# Audio-DAC-A.net
KiCad netlist of a schematic drawn in EAGLE
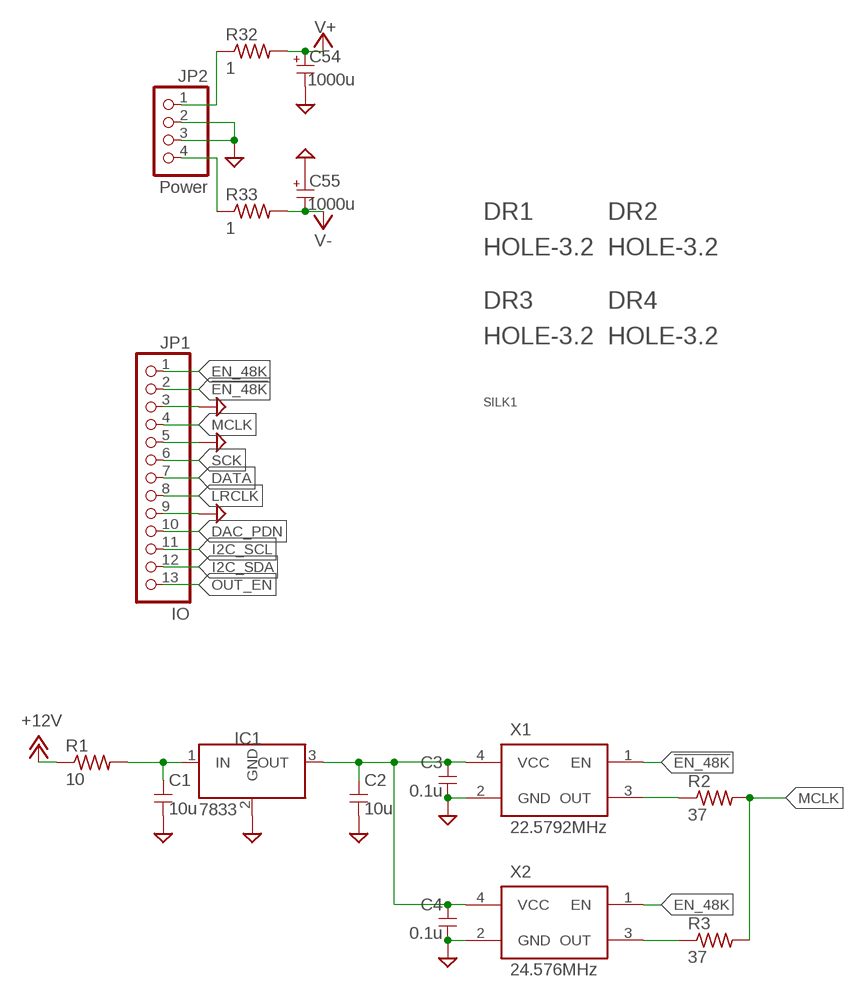
[diagram p0: schematic, sheet 1, part 1 of 2]
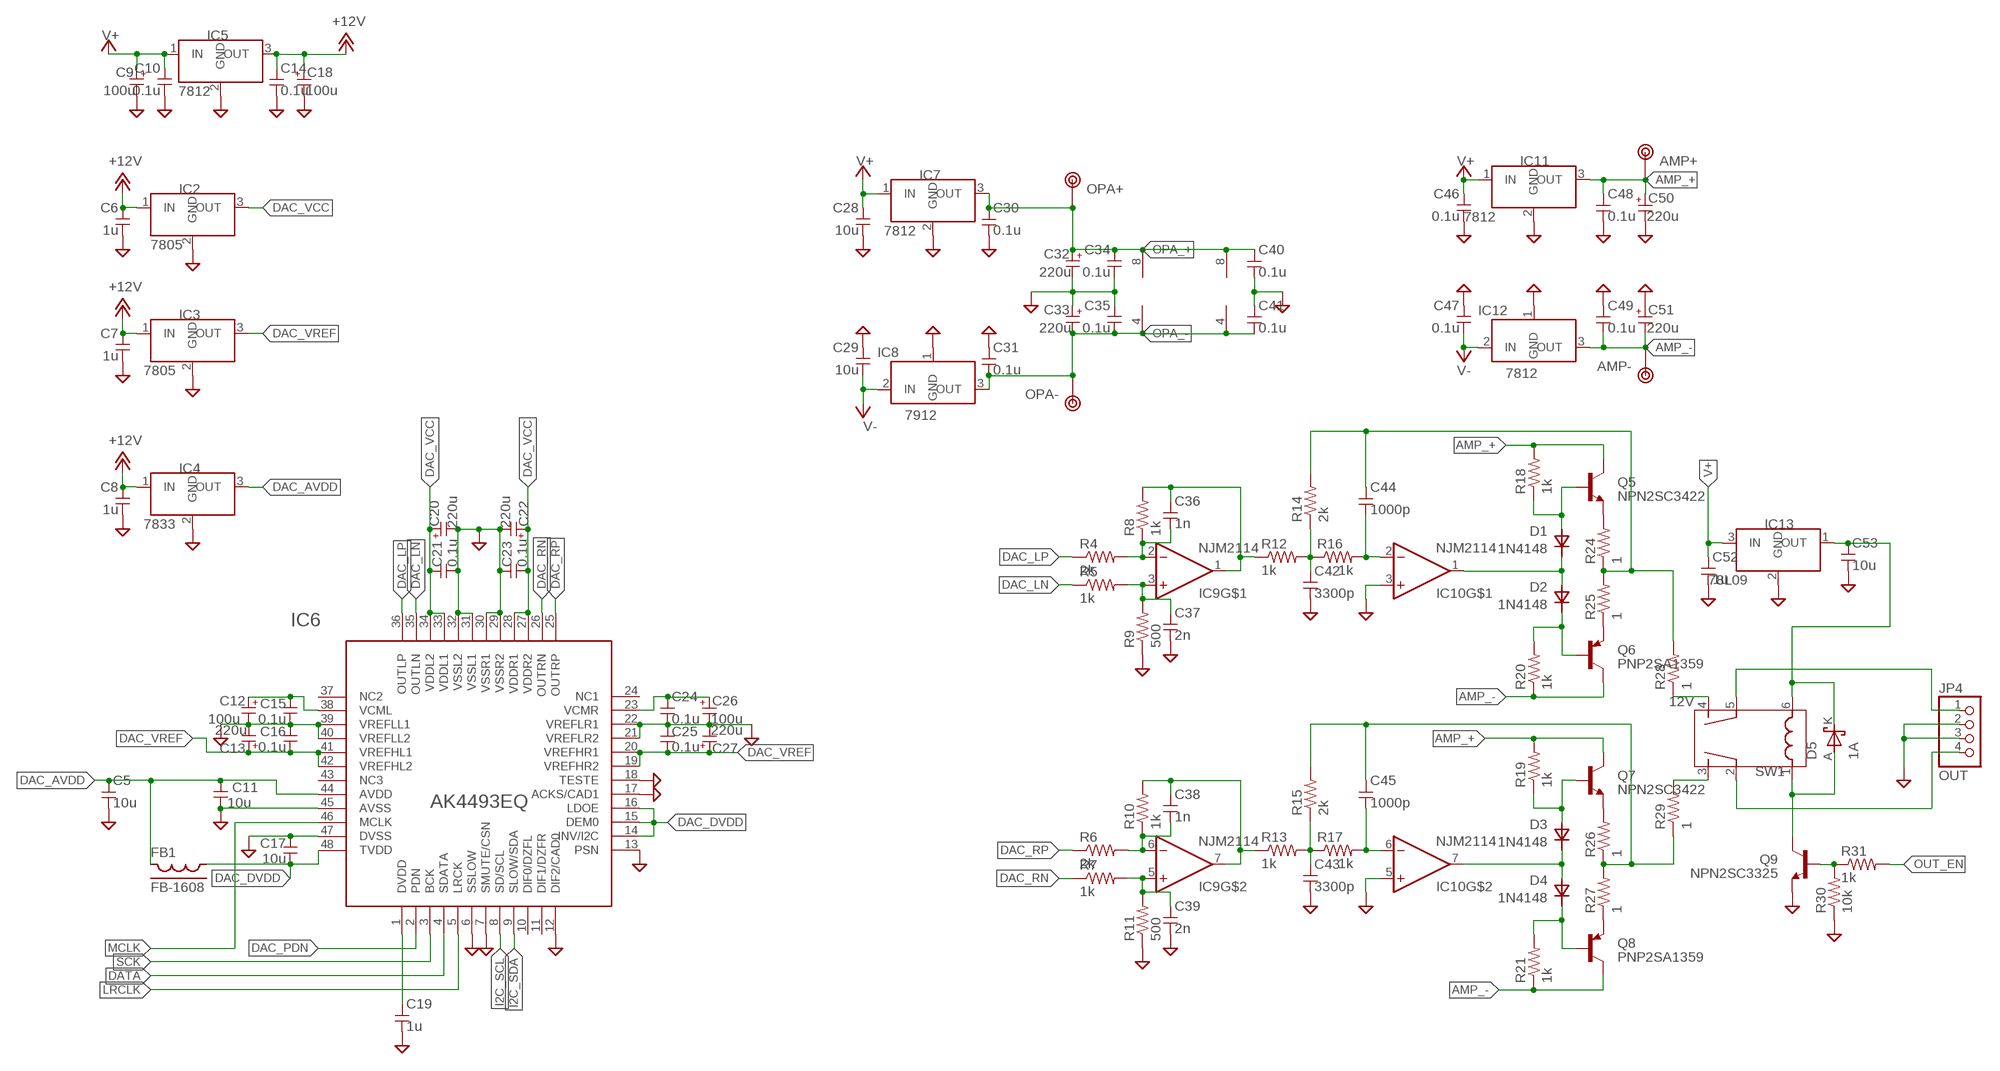
[diagram p1: schematic, sheet 1, part 2 of 2]

(export (version "E")
  (design (tool "Eeschema 10.0.6"))
  (components
    (comp (ref "C1")
      (value "10u")
      (footprint "eagle-import:2012")
      (libsource (lib "eagle-import") (part "C-2012"))
    )
    (comp (ref "C2")
      (value "10u")
      (footprint "eagle-import:2012")
      (libsource (lib "eagle-import") (part "C-2012"))
    )
    (comp (ref "C3")
      (value "0.1u")
      (footprint "eagle-import:1608")
      (libsource (lib "eagle-import") (part "C-1608"))
    )
    (comp (ref "C4")
      (value "0.1u")
      (footprint "eagle-import:1608")
      (libsource (lib "eagle-import") (part "C-1608"))
    )
    (comp (ref "C5")
      (value "10u")
      (footprint "eagle-import:2012")
      (libsource (lib "eagle-import") (part "C-2012"))
    )
    (comp (ref "C6")
      (value "1u")
      (footprint "eagle-import:1608")
      (libsource (lib "eagle-import") (part "C-1608"))
    )
    (comp (ref "C7")
      (value "1u")
      (footprint "eagle-import:1608")
      (libsource (lib "eagle-import") (part "C-1608"))
    )
    (comp (ref "C8")
      (value "1u")
      (footprint "eagle-import:1608")
      (libsource (lib "eagle-import") (part "C-1608"))
    )
    (comp (ref "C9")
      (value "100u")
      (footprint "eagle-import:E2,5-8")
      (libsource (lib "eagle-import") (part "CPOLE2.5-8"))
    )
    (comp (ref "C10")
      (value "0.1u")
      (footprint "eagle-import:1608")
      (libsource (lib "eagle-import") (part "C-1608"))
    )
    (comp (ref "C11")
      (value "10u")
      (footprint "eagle-import:1608")
      (libsource (lib "eagle-import") (part "C-1608"))
    )
    (comp (ref "C12")
      (value "100u")
      (footprint "eagle-import:E2.5-6.5")
      (libsource (lib "eagle-import") (part "CPOLE2.5-6.5"))
    )
    (comp (ref "C13")
      (value "220u")
      (footprint "eagle-import:E2.5-6.5")
      (libsource (lib "eagle-import") (part "CPOLE2.5-6.5"))
    )
    (comp (ref "C14")
      (value "0.1u")
      (footprint "eagle-import:1608")
      (libsource (lib "eagle-import") (part "C-1608"))
    )
    (comp (ref "C15")
      (value "0.1u")
      (footprint "eagle-import:1608")
      (libsource (lib "eagle-import") (part "C-1608"))
    )
    (comp (ref "C16")
      (value "0.1u")
      (footprint "eagle-import:1608")
      (libsource (lib "eagle-import") (part "C-1608"))
    )
    (comp (ref "C17")
      (value "10u")
      (footprint "eagle-import:1608")
      (libsource (lib "eagle-import") (part "C-1608"))
    )
    (comp (ref "C18")
      (value "100u")
      (footprint "eagle-import:E2,5-8")
      (libsource (lib "eagle-import") (part "CPOLE2.5-8"))
    )
    (comp (ref "C19")
      (value "1u")
      (footprint "eagle-import:1608")
      (libsource (lib "eagle-import") (part "C-1608"))
    )
    (comp (ref "C20")
      (value "220u")
      (footprint "eagle-import:E2.5-6.5")
      (libsource (lib "eagle-import") (part "CPOLE2.5-6.5"))
    )
    (comp (ref "C21")
      (value "0.1u")
      (footprint "eagle-import:1608")
      (libsource (lib "eagle-import") (part "C-1608"))
    )
    (comp (ref "C22")
      (value "220u")
      (footprint "eagle-import:E2.5-6.5")
      (libsource (lib "eagle-import") (part "CPOLE2.5-6.5"))
    )
    (comp (ref "C23")
      (value "0.1u")
      (footprint "eagle-import:1608")
      (libsource (lib "eagle-import") (part "C-1608"))
    )
    (comp (ref "C24")
      (value "0.1u")
      (footprint "eagle-import:1608")
      (libsource (lib "eagle-import") (part "C-1608"))
    )
    (comp (ref "C25")
      (value "0.1u")
      (footprint "eagle-import:1608")
      (libsource (lib "eagle-import") (part "C-1608"))
    )
    (comp (ref "C26")
      (value "100u")
      (footprint "eagle-import:E2.5-6.5")
      (libsource (lib "eagle-import") (part "CPOLE2.5-6.5"))
    )
    (comp (ref "C27")
      (value "220u")
      (footprint "eagle-import:E2.5-6.5")
      (libsource (lib "eagle-import") (part "CPOLE2.5-6.5"))
    )
    (comp (ref "C28")
      (value "10u")
      (footprint "eagle-import:1608")
      (libsource (lib "eagle-import") (part "C-1608"))
    )
    (comp (ref "C29")
      (value "10u")
      (footprint "eagle-import:1608")
      (libsource (lib "eagle-import") (part "C-1608"))
    )
    (comp (ref "C30")
      (value "0.1u")
      (footprint "eagle-import:1608")
      (libsource (lib "eagle-import") (part "C-1608"))
    )
    (comp (ref "C31")
      (value "0.1u")
      (footprint "eagle-import:1608")
      (libsource (lib "eagle-import") (part "C-1608"))
    )
    (comp (ref "C32")
      (value "220u")
      (footprint "eagle-import:E2.5-6.5")
      (libsource (lib "eagle-import") (part "CPOLE2.5-6.5"))
    )
    (comp (ref "C33")
      (value "220u")
      (footprint "eagle-import:E2.5-6.5")
      (libsource (lib "eagle-import") (part "CPOLE2.5-6.5"))
    )
    (comp (ref "C34")
      (value "0.1u")
      (footprint "eagle-import:1608")
      (libsource (lib "eagle-import") (part "C-1608"))
    )
    (comp (ref "C35")
      (value "0.1u")
      (footprint "eagle-import:1608")
      (libsource (lib "eagle-import") (part "C-1608"))
    )
    (comp (ref "C36")
      (value "1n")
      (footprint "eagle-import:1608")
      (libsource (lib "eagle-import") (part "C-1608"))
    )
    (comp (ref "C37")
      (value "2n")
      (footprint "eagle-import:1608")
      (libsource (lib "eagle-import") (part "C-1608"))
    )
    (comp (ref "C38")
      (value "1n")
      (footprint "eagle-import:1608")
      (libsource (lib "eagle-import") (part "C-1608"))
    )
    (comp (ref "C39")
      (value "2n")
      (footprint "eagle-import:1608")
      (libsource (lib "eagle-import") (part "C-1608"))
    )
    (comp (ref "C40")
      (value "0.1u")
      (footprint "eagle-import:1608")
      (libsource (lib "eagle-import") (part "C-1608"))
    )
    (comp (ref "C41")
      (value "0.1u")
      (footprint "eagle-import:1608")
      (libsource (lib "eagle-import") (part "C-1608"))
    )
    (comp (ref "C42")
      (value "3300p")
      (footprint "eagle-import:1608")
      (libsource (lib "eagle-import") (part "C-1608"))
    )
    (comp (ref "C43")
      (value "3300p")
      (footprint "eagle-import:1608")
      (libsource (lib "eagle-import") (part "C-1608"))
    )
    (comp (ref "C44")
      (value "1000p")
      (footprint "eagle-import:1608")
      (libsource (lib "eagle-import") (part "C-1608"))
    )
    (comp (ref "C45")
      (value "1000p")
      (footprint "eagle-import:1608")
      (libsource (lib "eagle-import") (part "C-1608"))
    )
    (comp (ref "C46")
      (value "0.1u")
      (footprint "eagle-import:1608")
      (libsource (lib "eagle-import") (part "C-1608"))
    )
    (comp (ref "C47")
      (value "0.1u")
      (footprint "eagle-import:1608")
      (libsource (lib "eagle-import") (part "C-1608"))
    )
    (comp (ref "C48")
      (value "0.1u")
      (footprint "eagle-import:1608")
      (libsource (lib "eagle-import") (part "C-1608"))
    )
    (comp (ref "C49")
      (value "0.1u")
      (footprint "eagle-import:1608")
      (libsource (lib "eagle-import") (part "C-1608"))
    )
    (comp (ref "C50")
      (value "220u")
      (footprint "eagle-import:E5-10")
      (libsource (lib "eagle-import") (part "CPOLE5-10"))
    )
    (comp (ref "C51")
      (value "220u")
      (footprint "eagle-import:E5-10")
      (libsource (lib "eagle-import") (part "CPOLE5-10"))
    )
    (comp (ref "C52")
      (value "1u")
      (footprint "eagle-import:1608")
      (libsource (lib "eagle-import") (part "C-1608"))
    )
    (comp (ref "C53")
      (value "10u")
      (footprint "eagle-import:2012")
      (libsource (lib "eagle-import") (part "C-2012"))
    )
    (comp (ref "C54")
      (value "1000u")
      (footprint "eagle-import:E5-10")
      (libsource (lib "eagle-import") (part "CPOLE5-10"))
    )
    (comp (ref "C55")
      (value "1000u")
      (footprint "eagle-import:E5-10")
      (libsource (lib "eagle-import") (part "CPOLE5-10"))
    )
    (comp (ref "D1")
      (value "1N4148")
      (footprint "eagle-import:D0207_2V")
      (libsource (lib "eagle-import") (part "DIODE-2"))
    )
    (comp (ref "D2")
      (value "1N4148")
      (footprint "eagle-import:D0207_2V")
      (libsource (lib "eagle-import") (part "DIODE-2"))
    )
    (comp (ref "D3")
      (value "1N4148")
      (footprint "eagle-import:D0207_2V")
      (libsource (lib "eagle-import") (part "DIODE-2"))
    )
    (comp (ref "D4")
      (value "1N4148")
      (footprint "eagle-import:D0207_2V")
      (libsource (lib "eagle-import") (part "DIODE-2"))
    )
    (comp (ref "D5")
      (value "1A")
      (footprint "eagle-import:TUMD2M")
      (libsource (lib "eagle-import") (part "SBD-1A"))
    )
    (comp (ref "DR1")
      (value "HOLE-3.2")
      (footprint "eagle-import:HOLE_3.2")
      (libsource (lib "eagle-import") (part "HOLE-3.2"))
    )
    (comp (ref "DR2")
      (value "HOLE-3.2")
      (footprint "eagle-import:HOLE_3.2")
      (libsource (lib "eagle-import") (part "HOLE-3.2"))
    )
    (comp (ref "DR3")
      (value "HOLE-3.2")
      (footprint "eagle-import:HOLE_3.2")
      (libsource (lib "eagle-import") (part "HOLE-3.2"))
    )
    (comp (ref "DR4")
      (value "HOLE-3.2")
      (footprint "eagle-import:HOLE_3.2")
      (libsource (lib "eagle-import") (part "HOLE-3.2"))
    )
    (comp (ref "FB1")
      (value "FB-1608")
      (footprint "eagle-import:1608")
      (libsource (lib "eagle-import") (part "FB-1608"))
    )
    (comp (ref "IC1")
      (value "7833")
      (footprint "eagle-import:7805-LARGEHOLE")
      (libsource (lib "eagle-import") (part "78X-1"))
    )
    (comp (ref "IC2")
      (value "7805")
      (footprint "eagle-import:7805-LARGEHOLE")
      (libsource (lib "eagle-import") (part "78X-1"))
    )
    (comp (ref "IC3")
      (value "7805")
      (footprint "eagle-import:7805-LARGEHOLE")
      (libsource (lib "eagle-import") (part "78X-1"))
    )
    (comp (ref "IC4")
      (value "7833")
      (footprint "eagle-import:7805-LARGEHOLE")
      (libsource (lib "eagle-import") (part "78X-1"))
    )
    (comp (ref "IC5")
      (value "7812")
      (footprint "eagle-import:7805-LARGEHOLE")
      (libsource (lib "eagle-import") (part "78X-1"))
    )
    (comp (ref "IC6")
      (value "AK4493EQ")
      (footprint "eagle-import:LQFP48")
      (libsource (lib "eagle-import") (part "AK4493EQ"))
    )
    (comp (ref "IC7")
      (value "7812")
      (footprint "eagle-import:7805-LARGEHOLE")
      (libsource (lib "eagle-import") (part "78X-1"))
    )
    (comp (ref "IC8")
      (value "7912")
      (footprint "eagle-import:7805-LARGEHOLE")
      (libsource (lib "eagle-import") (part "79X-1"))
    )
    (comp (ref "IC9")
      (value "NJM2114")
      (footprint "eagle-import:DIL08")
      (libsource (lib "eagle-import") (part "OPA-2'"))
    )
    (comp (ref "IC10")
      (value "NJM2114")
      (footprint "eagle-import:DIL08")
      (libsource (lib "eagle-import") (part "OPA-2'"))
    )
    (comp (ref "IC11")
      (value "7812")
      (footprint "eagle-import:7805-LARGEHOLE")
      (libsource (lib "eagle-import") (part "78X-1"))
    )
    (comp (ref "IC12")
      (value "7812")
      (footprint "eagle-import:7805-LARGEHOLE")
      (libsource (lib "eagle-import") (part "79X-1"))
    )
    (comp (ref "IC13")
      (value "78L09")
      (footprint "eagle-import:TO-92")
      (libsource (lib "eagle-import") (part "78LX"))
    )
    (comp (ref "JP1")
      (value "IO")
      (footprint "eagle-import:1X13")
      (libsource (lib "eagle-import") (part "PINHD-1X13"))
    )
    (comp (ref "JP2")
      (value "Power")
      (footprint "eagle-import:1X04")
      (libsource (lib "eagle-import") (part "PINHD-1X4"))
    )
    (comp (ref "JP4")
      (value "OUT")
      (footprint "eagle-import:1X04")
      (libsource (lib "eagle-import") (part "PINHD-1X4"))
    )
    (comp (ref "Q5")
      (value "NPN2SC3422")
      (footprint "eagle-import:TO126")
      (libsource (lib "eagle-import") (part "NPN2SC3422"))
    )
    (comp (ref "Q6")
      (value "PNP2SA1359")
      (footprint "eagle-import:TO126")
      (libsource (lib "eagle-import") (part "PNP2SA1359"))
    )
    (comp (ref "Q7")
      (value "NPN2SC3422")
      (footprint "eagle-import:TO126")
      (libsource (lib "eagle-import") (part "NPN2SC3422"))
    )
    (comp (ref "Q8")
      (value "PNP2SA1359")
      (footprint "eagle-import:TO126")
      (libsource (lib "eagle-import") (part "PNP2SA1359"))
    )
    (comp (ref "Q9")
      (value "NPN2SC3325")
      (footprint "eagle-import:SC59")
      (libsource (lib "eagle-import") (part "NPN2SC3325"))
    )
    (comp (ref "R1")
      (value "10")
      (footprint "eagle-import:0204_7")
      (libsource (lib "eagle-import") (part "R-7.5"))
    )
    (comp (ref "R2")
      (value "37")
      (footprint "eagle-import:1608")
      (libsource (lib "eagle-import") (part "R-1608"))
    )
    (comp (ref "R3")
      (value "37")
      (footprint "eagle-import:1608")
      (libsource (lib "eagle-import") (part "R-1608"))
    )
    (comp (ref "R4")
      (value "2k")
      (footprint "eagle-import:0207_2V")
      (libsource (lib "eagle-import") (part "R-2.5"))
    )
    (comp (ref "R5")
      (value "1k")
      (footprint "eagle-import:0207_2V")
      (libsource (lib "eagle-import") (part "R-2.5"))
    )
    (comp (ref "R6")
      (value "2k")
      (footprint "eagle-import:0207_2V")
      (libsource (lib "eagle-import") (part "R-2.5"))
    )
    (comp (ref "R7")
      (value "1k")
      (footprint "eagle-import:0207_2V")
      (libsource (lib "eagle-import") (part "R-2.5"))
    )
    (comp (ref "R8")
      (value "1k")
      (footprint "eagle-import:0207_2V")
      (libsource (lib "eagle-import") (part "R-2.5"))
    )
    (comp (ref "R9")
      (value "500")
      (footprint "eagle-import:0207_2V")
      (libsource (lib "eagle-import") (part "R-2.5"))
    )
    (comp (ref "R10")
      (value "1k")
      (footprint "eagle-import:0207_2V")
      (libsource (lib "eagle-import") (part "R-2.5"))
    )
    (comp (ref "R11")
      (value "500")
      (footprint "eagle-import:0207_2V")
      (libsource (lib "eagle-import") (part "R-2.5"))
    )
    (comp (ref "R12")
      (value "1k")
      (footprint "eagle-import:0207_2V")
      (libsource (lib "eagle-import") (part "R-2.5"))
    )
    (comp (ref "R13")
      (value "1k")
      (footprint "eagle-import:0207_2V")
      (libsource (lib "eagle-import") (part "R-2.5"))
    )
    (comp (ref "R14")
      (value "2k")
      (footprint "eagle-import:0207_2V")
      (libsource (lib "eagle-import") (part "R-2.5"))
    )
    (comp (ref "R15")
      (value "2k")
      (footprint "eagle-import:0207_2V")
      (libsource (lib "eagle-import") (part "R-2.5"))
    )
    (comp (ref "R16")
      (value "1k")
      (footprint "eagle-import:0207_2V")
      (libsource (lib "eagle-import") (part "R-2.5"))
    )
    (comp (ref "R17")
      (value "1k")
      (footprint "eagle-import:0207_2V")
      (libsource (lib "eagle-import") (part "R-2.5"))
    )
    (comp (ref "R18")
      (value "1k")
      (footprint "eagle-import:0207_2V")
      (libsource (lib "eagle-import") (part "R-2.5"))
    )
    (comp (ref "R19")
      (value "1k")
      (footprint "eagle-import:0207_2V")
      (libsource (lib "eagle-import") (part "R-2.5"))
    )
    (comp (ref "R20")
      (value "1k")
      (footprint "eagle-import:0207_2V")
      (libsource (lib "eagle-import") (part "R-2.5"))
    )
    (comp (ref "R21")
      (value "1k")
      (footprint "eagle-import:0207_2V")
      (libsource (lib "eagle-import") (part "R-2.5"))
    )
    (comp (ref "R24")
      (value "1")
      (footprint "eagle-import:0207_2V")
      (libsource (lib "eagle-import") (part "R-2.5"))
    )
    (comp (ref "R25")
      (value "1")
      (footprint "eagle-import:0207_2V")
      (libsource (lib "eagle-import") (part "R-2.5"))
    )
    (comp (ref "R26")
      (value "1")
      (footprint "eagle-import:0207_2V")
      (libsource (lib "eagle-import") (part "R-2.5"))
    )
    (comp (ref "R27")
      (value "1")
      (footprint "eagle-import:0207_2V")
      (libsource (lib "eagle-import") (part "R-2.5"))
    )
    (comp (ref "R28")
      (value "1")
      (footprint "eagle-import:0207_2V")
      (libsource (lib "eagle-import") (part "R-2.5"))
    )
    (comp (ref "R29")
      (value "1")
      (footprint "eagle-import:0207_2V")
      (libsource (lib "eagle-import") (part "R-2.5"))
    )
    (comp (ref "R30")
      (value "10k")
      (footprint "eagle-import:1608")
      (libsource (lib "eagle-import") (part "R-1608"))
    )
    (comp (ref "R31")
      (value "1k")
      (footprint "eagle-import:0204_7")
      (libsource (lib "eagle-import") (part "R-7.5"))
    )
    (comp (ref "R32")
      (value "1")
      (footprint "eagle-import:0207_10")
      (libsource (lib "eagle-import") (part "R-10"))
    )
    (comp (ref "R33")
      (value "1")
      (footprint "eagle-import:0207_10")
      (libsource (lib "eagle-import") (part "R-10"))
    )
    (comp (ref "SILK1")
      (value "ROBOTECHWHEELSILK-9MM")
      (footprint "eagle-import:ROBOTECHWHEEL-9MM")
      (libsource (lib "eagle-import") (part "ROBOTECHWHEELSILK-9MM"))
    )
    (comp (ref "SW1")
      (value "12V")
      (footprint "eagle-import:ALA2F")
      (libsource (lib "eagle-import") (part "ALA2F"))
    )
    (comp (ref "TP1")
      (value "AMP+")
      (footprint "eagle-import:TESTPIN")
      (libsource (lib "eagle-import") (part "TESTPIN"))
    )
    (comp (ref "TP2")
      (value "AMP-")
      (footprint "eagle-import:TESTPIN")
      (libsource (lib "eagle-import") (part "TESTPIN"))
    )
    (comp (ref "TP3")
      (value "OPA-")
      (footprint "eagle-import:TESTPIN")
      (libsource (lib "eagle-import") (part "TESTPIN"))
    )
    (comp (ref "TP4")
      (value "OPA+")
      (footprint "eagle-import:TESTPIN")
      (libsource (lib "eagle-import") (part "TESTPIN"))
    )
    (comp (ref "X1")
      (value "22.5792MHz")
      (footprint "eagle-import:KC7050")
      (libsource (lib "eagle-import") (part "OSC-KC7050"))
    )
    (comp (ref "X2")
      (value "24.576MHz")
      (footprint "eagle-import:KC7050")
      (libsource (lib "eagle-import") (part "OSC-KC7050"))
    )
  )
  (nets
    (net (code "1") (name "+12V") (class "Default")
      (node (ref "C14") (pin "1") (pinfunction "1_1") (pintype "passive"))
      (node (ref "C18") (pin "+") (pinfunction "1_+") (pintype "passive"))
      (node (ref "C6") (pin "1") (pinfunction "1_1") (pintype "passive"))
      (node (ref "C7") (pin "1") (pinfunction "1_1") (pintype "passive"))
      (node (ref "C8") (pin "1") (pinfunction "1_1") (pintype "passive"))
      (node (ref "IC2") (pin "1") (pinfunction "IN_1") (pintype "power_in"))
      (node (ref "IC3") (pin "1") (pinfunction "IN_1") (pintype "power_in"))
      (node (ref "IC4") (pin "1") (pinfunction "IN_1") (pintype "power_in"))
      (node (ref "IC5") (pin "3") (pinfunction "OUT_3") (pintype "output"))
      (node (ref "R1") (pin "1") (pinfunction "1_1") (pintype "passive"))
    )
    (net (code "2") (name "/~{EN_48K}") (class "Default")
      (node (ref "JP1") (pin "2") (pinfunction "2_2") (pintype "passive"))
      (node (ref "X1") (pin "1") (pinfunction "EN_1") (pintype "input"))
    )
    (net (code "3") (name "AMP_+") (class "Default")
      (node (ref "C48") (pin "1") (pinfunction "1_1") (pintype "passive"))
      (node (ref "C50") (pin "+") (pinfunction "1_+") (pintype "passive"))
      (node (ref "IC11") (pin "3") (pinfunction "OUT_3") (pintype "output"))
      (node (ref "Q5") (pin "2") (pinfunction "C_2") (pintype "passive"))
      (node (ref "Q7") (pin "2") (pinfunction "C_2") (pintype "passive"))
      (node (ref "R18") (pin "2") (pinfunction "2_2") (pintype "passive"))
      (node (ref "R19") (pin "2") (pinfunction "2_2") (pintype "passive"))
      (node (ref "TP1") (pin "1") (pinfunction "1_1") (pintype "passive"))
    )
    (net (code "4") (name "AMP_-") (class "Default")
      (node (ref "C49") (pin "2") (pinfunction "2_2") (pintype "passive"))
      (node (ref "C51") (pin "-") (pinfunction "2_-") (pintype "passive"))
      (node (ref "IC12") (pin "3") (pinfunction "OUT_3") (pintype "output"))
      (node (ref "Q6") (pin "2") (pinfunction "C_2") (pintype "passive"))
      (node (ref "Q8") (pin "2") (pinfunction "C_2") (pintype "passive"))
      (node (ref "R20") (pin "1") (pinfunction "1_1") (pintype "passive"))
      (node (ref "R21") (pin "1") (pinfunction "1_1") (pintype "passive"))
      (node (ref "TP2") (pin "1") (pinfunction "1_1") (pintype "passive"))
    )
    (net (code "5") (name "DAC_AVDD") (class "Default")
      (node (ref "C11") (pin "1") (pinfunction "1_1") (pintype "passive"))
      (node (ref "C5") (pin "1") (pinfunction "1_1") (pintype "passive"))
      (node (ref "FB1") (pin "2") (pinfunction "2_2") (pintype "passive"))
      (node (ref "IC4") (pin "3") (pinfunction "OUT_3") (pintype "output"))
      (node (ref "IC6") (pin "44") (pinfunction "AVDD_44") (pintype "power_in"))
    )
    (net (code "6") (name "DAC_DVDD") (class "Default")
      (node (ref "C17") (pin "2") (pinfunction "2_2") (pintype "passive"))
      (node (ref "FB1") (pin "1") (pinfunction "1_1") (pintype "passive"))
      (node (ref "IC6") (pin "14") (pinfunction "INV/I2C_14") (pintype "input"))
      (node (ref "IC6") (pin "15") (pinfunction "DEM0_15") (pintype "input"))
      (node (ref "IC6") (pin "16") (pinfunction "LDOE_16") (pintype "bidirectional"))
      (node (ref "IC6") (pin "48") (pinfunction "TVDD_48") (pintype "power_in"))
    )
    (net (code "7") (name "DAC_LN") (class "Default")
      (node (ref "IC6") (pin "35") (pinfunction "OUTLN_35") (pintype "output"))
      (node (ref "R5") (pin "1") (pinfunction "1_1") (pintype "passive"))
    )
    (net (code "8") (name "DAC_LP") (class "Default")
      (node (ref "IC6") (pin "36") (pinfunction "OUTLP_36") (pintype "output"))
      (node (ref "R4") (pin "1") (pinfunction "1_1") (pintype "passive"))
    )
    (net (code "9") (name "DAC_PDN") (class "Default")
      (node (ref "IC6") (pin "2") (pinfunction "PDN_2") (pintype "input"))
      (node (ref "JP1") (pin "10") (pinfunction "10_10") (pintype "passive"))
    )
    (net (code "10") (name "DAC_RN") (class "Default")
      (node (ref "IC6") (pin "26") (pinfunction "OUTRN_26") (pintype "output"))
      (node (ref "R7") (pin "1") (pinfunction "1_1") (pintype "passive"))
    )
    (net (code "11") (name "DAC_RP") (class "Default")
      (node (ref "IC6") (pin "25") (pinfunction "OUTRP_25") (pintype "output"))
      (node (ref "R6") (pin "1") (pinfunction "1_1") (pintype "passive"))
    )
    (net (code "12") (name "DAC_VCC") (class "Default")
      (node (ref "C20") (pin "+") (pinfunction "1_+") (pintype "passive"))
      (node (ref "C21") (pin "1") (pinfunction "1_1") (pintype "passive"))
      (node (ref "C22") (pin "+") (pinfunction "1_+") (pintype "passive"))
      (node (ref "C23") (pin "2") (pinfunction "2_2") (pintype "passive"))
      (node (ref "IC2") (pin "3") (pinfunction "OUT_3") (pintype "output"))
      (node (ref "IC6") (pin "27") (pinfunction "VDDR2_27") (pintype "power_in"))
      (node (ref "IC6") (pin "28") (pinfunction "VDDR1_28") (pintype "power_in"))
      (node (ref "IC6") (pin "33") (pinfunction "VDDL1_33") (pintype "power_in"))
      (node (ref "IC6") (pin "34") (pinfunction "VDDL2_34") (pintype "power_in"))
    )
    (net (code "13") (name "DAC_VREF") (class "Default")
      (node (ref "C13") (pin "+") (pinfunction "1_+") (pintype "passive"))
      (node (ref "C16") (pin "2") (pinfunction "2_2") (pintype "passive"))
      (node (ref "C25") (pin "2") (pinfunction "2_2") (pintype "passive"))
      (node (ref "C27") (pin "+") (pinfunction "1_+") (pintype "passive"))
      (node (ref "IC3") (pin "3") (pinfunction "OUT_3") (pintype "output"))
      (node (ref "IC6") (pin "19") (pinfunction "VREFHR2_19") (pintype "power_in"))
      (node (ref "IC6") (pin "20") (pinfunction "VREFHR1_20") (pintype "power_in"))
      (node (ref "IC6") (pin "41") (pinfunction "VREFHL1_41") (pintype "power_in"))
      (node (ref "IC6") (pin "42") (pinfunction "VREFHL2_42") (pintype "power_in"))
    )
    (net (code "14") (name "DATA") (class "Default")
      (node (ref "IC6") (pin "4") (pinfunction "SDATA_4") (pintype "input"))
      (node (ref "JP1") (pin "7") (pinfunction "7_7") (pintype "passive"))
    )
    (net (code "15") (name "EN_48K") (class "Default")
      (node (ref "JP1") (pin "1") (pinfunction "1_1") (pintype "passive"))
      (node (ref "X2") (pin "1") (pinfunction "EN_1") (pintype "input"))
    )
    (net (code "16") (name "GND") (class "Default")
      (node (ref "C1") (pin "2") (pinfunction "2_2") (pintype "passive"))
      (node (ref "C10") (pin "2") (pinfunction "2_2") (pintype "passive"))
      (node (ref "C11") (pin "2") (pinfunction "2_2") (pintype "passive"))
      (node (ref "C12") (pin "-") (pinfunction "2_-") (pintype "passive"))
      (node (ref "C13") (pin "-") (pinfunction "2_-") (pintype "passive"))
      (node (ref "C14") (pin "2") (pinfunction "2_2") (pintype "passive"))
      (node (ref "C15") (pin "2") (pinfunction "2_2") (pintype "passive"))
      (node (ref "C16") (pin "1") (pinfunction "1_1") (pintype "passive"))
      (node (ref "C17") (pin "1") (pinfunction "1_1") (pintype "passive"))
      (node (ref "C18") (pin "-") (pinfunction "2_-") (pintype "passive"))
      (node (ref "C19") (pin "2") (pinfunction "2_2") (pintype "passive"))
      (node (ref "C2") (pin "2") (pinfunction "2_2") (pintype "passive"))
      (node (ref "C20") (pin "-") (pinfunction "2_-") (pintype "passive"))
      (node (ref "C21") (pin "2") (pinfunction "2_2") (pintype "passive"))
      (node (ref "C22") (pin "-") (pinfunction "2_-") (pintype "passive"))
      (node (ref "C23") (pin "1") (pinfunction "1_1") (pintype "passive"))
      (node (ref "C24") (pin "2") (pinfunction "2_2") (pintype "passive"))
      (node (ref "C25") (pin "1") (pinfunction "1_1") (pintype "passive"))
      (node (ref "C26") (pin "-") (pinfunction "2_-") (pintype "passive"))
      (node (ref "C27") (pin "-") (pinfunction "2_-") (pintype "passive"))
      (node (ref "C28") (pin "2") (pinfunction "2_2") (pintype "passive"))
      (node (ref "C29") (pin "1") (pinfunction "1_1") (pintype "passive"))
      (node (ref "C3") (pin "2") (pinfunction "2_2") (pintype "passive"))
      (node (ref "C30") (pin "2") (pinfunction "2_2") (pintype "passive"))
      (node (ref "C31") (pin "1") (pinfunction "1_1") (pintype "passive"))
      (node (ref "C32") (pin "-") (pinfunction "2_-") (pintype "passive"))
      (node (ref "C33") (pin "+") (pinfunction "1_+") (pintype "passive"))
      (node (ref "C34") (pin "2") (pinfunction "2_2") (pintype "passive"))
      (node (ref "C35") (pin "1") (pinfunction "1_1") (pintype "passive"))
      (node (ref "C37") (pin "2") (pinfunction "2_2") (pintype "passive"))
      (node (ref "C39") (pin "2") (pinfunction "2_2") (pintype "passive"))
      (node (ref "C4") (pin "2") (pinfunction "2_2") (pintype "passive"))
      (node (ref "C40") (pin "2") (pinfunction "2_2") (pintype "passive"))
      (node (ref "C41") (pin "1") (pinfunction "1_1") (pintype "passive"))
      (node (ref "C42") (pin "2") (pinfunction "2_2") (pintype "passive"))
      (node (ref "C43") (pin "2") (pinfunction "2_2") (pintype "passive"))
      (node (ref "C46") (pin "2") (pinfunction "2_2") (pintype "passive"))
      (node (ref "C47") (pin "1") (pinfunction "1_1") (pintype "passive"))
      (node (ref "C48") (pin "2") (pinfunction "2_2") (pintype "passive"))
      (node (ref "C49") (pin "1") (pinfunction "1_1") (pintype "passive"))
      (node (ref "C5") (pin "2") (pinfunction "2_2") (pintype "passive"))
      (node (ref "C50") (pin "-") (pinfunction "2_-") (pintype "passive"))
      (node (ref "C51") (pin "+") (pinfunction "1_+") (pintype "passive"))
      (node (ref "C52") (pin "2") (pinfunction "2_2") (pintype "passive"))
      (node (ref "C53") (pin "2") (pinfunction "2_2") (pintype "passive"))
      (node (ref "C54") (pin "-") (pinfunction "2_-") (pintype "passive"))
      (node (ref "C55") (pin "+") (pinfunction "1_+") (pintype "passive"))
      (node (ref "C6") (pin "2") (pinfunction "2_2") (pintype "passive"))
      (node (ref "C7") (pin "2") (pinfunction "2_2") (pintype "passive"))
      (node (ref "C8") (pin "2") (pinfunction "2_2") (pintype "passive"))
      (node (ref "C9") (pin "-") (pinfunction "2_-") (pintype "passive"))
      (node (ref "IC1") (pin "2") (pinfunction "GND_2") (pintype "power_in"))
      (node (ref "IC10") (pin "3") (pinfunction "+IN_3") (pintype "input"))
      (node (ref "IC10") (pin "5") (pinfunction "+IN_5") (pintype "input"))
      (node (ref "IC11") (pin "2") (pinfunction "GND_2") (pintype "power_in"))
      (node (ref "IC12") (pin "1") (pinfunction "GND_1") (pintype "input"))
      (node (ref "IC13") (pin "2") (pinfunction "GND_2") (pintype "power_in"))
      (node (ref "IC2") (pin "2") (pinfunction "GND_2") (pintype "power_in"))
      (node (ref "IC3") (pin "2") (pinfunction "GND_2") (pintype "power_in"))
      (node (ref "IC4") (pin "2") (pinfunction "GND_2") (pintype "power_in"))
      (node (ref "IC5") (pin "2") (pinfunction "GND_2") (pintype "power_in"))
      (node (ref "IC6") (pin "12") (pinfunction "DIF2/CAD0_12") (pintype "input"))
      (node (ref "IC6") (pin "13") (pinfunction "PSN_13") (pintype "input"))
      (node (ref "IC6") (pin "17") (pinfunction "ACKS/CAD1_17") (pintype "input"))
      (node (ref "IC6") (pin "18") (pinfunction "TESTE_18") (pintype "input"))
      (node (ref "IC6") (pin "21") (pinfunction "VREFLR2_21") (pintype "power_in"))
      (node (ref "IC6") (pin "22") (pinfunction "VREFLR1_22") (pintype "power_in"))
      (node (ref "IC6") (pin "29") (pinfunction "VSSR2_29") (pintype "power_in"))
      (node (ref "IC6") (pin "30") (pinfunction "VSSR1_30") (pintype "power_in"))
      (node (ref "IC6") (pin "31") (pinfunction "VSSL1_31") (pintype "power_in"))
      (node (ref "IC6") (pin "32") (pinfunction "VSSL2_32") (pintype "power_in"))
      (node (ref "IC6") (pin "39") (pinfunction "VREFLL1_39") (pintype "power_in"))
      (node (ref "IC6") (pin "40") (pinfunction "VREFLL2_40") (pintype "power_in"))
      (node (ref "IC6") (pin "45") (pinfunction "AVSS_45") (pintype "power_in"))
      (node (ref "IC6") (pin "47") (pinfunction "DVSS_47") (pintype "power_in"))
      (node (ref "IC6") (pin "6") (pinfunction "SSLOW_6") (pintype "input"))
      (node (ref "IC6") (pin "7") (pinfunction "SMUTE/CSN_7") (pintype "input"))
      (node (ref "IC7") (pin "2") (pinfunction "GND_2") (pintype "power_in"))
      (node (ref "IC8") (pin "1") (pinfunction "GND_1") (pintype "input"))
      (node (ref "JP1") (pin "3") (pinfunction "3_3") (pintype "passive"))
      (node (ref "JP1") (pin "5") (pinfunction "5_5") (pintype "passive"))
      (node (ref "JP1") (pin "9") (pinfunction "9_9") (pintype "passive"))
      (node (ref "JP2") (pin "2") (pinfunction "2_2") (pintype "passive"))
      (node (ref "JP2") (pin "3") (pinfunction "3_3") (pintype "passive"))
      (node (ref "JP4") (pin "2") (pinfunction "2_2") (pintype "passive"))
      (node (ref "JP4") (pin "3") (pinfunction "3_3") (pintype "passive"))
      (node (ref "Q9") (pin "2") (pinfunction "E_2") (pintype "passive"))
      (node (ref "R11") (pin "1") (pinfunction "1_1") (pintype "passive"))
      (node (ref "R30") (pin "1") (pinfunction "1_1") (pintype "passive"))
      (node (ref "R9") (pin "1") (pinfunction "1_1") (pintype "passive"))
      (node (ref "X1") (pin "2") (pinfunction "GND_2") (pintype "power_in"))
      (node (ref "X2") (pin "2") (pinfunction "GND_2") (pintype "power_in"))
    )
    (net (code "17") (name "I2C_SCL") (class "Default")
      (node (ref "IC6") (pin "8") (pinfunction "SD/SCL_8") (pintype "bidirectional"))
      (node (ref "JP1") (pin "11") (pinfunction "11_11") (pintype "passive"))
    )
    (net (code "18") (name "I2C_SDA") (class "Default")
      (node (ref "IC6") (pin "9") (pinfunction "SLOW/SDA_9") (pintype "bidirectional"))
      (node (ref "JP1") (pin "12") (pinfunction "12_12") (pintype "passive"))
    )
    (net (code "19") (name "LRCLK") (class "Default")
      (node (ref "IC6") (pin "5") (pinfunction "LRCK_5") (pintype "input"))
      (node (ref "JP1") (pin "8") (pinfunction "8_8") (pintype "passive"))
    )
    (net (code "20") (name "MCLK") (class "Default")
      (node (ref "IC6") (pin "46") (pinfunction "MCLK_46") (pintype "input"))
      (node (ref "JP1") (pin "4") (pinfunction "4_4") (pintype "passive"))
      (node (ref "R2") (pin "2") (pinfunction "2_2") (pintype "passive"))
      (node (ref "R3") (pin "2") (pinfunction "2_2") (pintype "passive"))
    )
    (net (code "21") (name "Net-(C12-1)") (class "Default")
      (node (ref "C12") (pin "+") (pinfunction "1_+") (pintype "passive"))
      (node (ref "C15") (pin "1") (pinfunction "1_1") (pintype "passive"))
      (node (ref "IC6") (pin "38") (pinfunction "VCML_38") (pintype "power_in"))
    )
    (net (code "22") (name "Net-(C26-1)") (class "Default")
      (node (ref "C24") (pin "1") (pinfunction "1_1") (pintype "passive"))
      (node (ref "C26") (pin "+") (pinfunction "1_+") (pintype "passive"))
      (node (ref "IC6") (pin "23") (pinfunction "VCMR_23") (pintype "power_in"))
    )
    (net (code "23") (name "Net-(C42-Pad1)") (class "Default")
      (node (ref "C42") (pin "1") (pinfunction "1_1") (pintype "passive"))
      (node (ref "R12") (pin "2") (pinfunction "2_2") (pintype "passive"))
      (node (ref "R14") (pin "1") (pinfunction "1_1") (pintype "passive"))
      (node (ref "R16") (pin "1") (pinfunction "1_1") (pintype "passive"))
    )
    (net (code "24") (name "Net-(C43-Pad1)") (class "Default")
      (node (ref "C43") (pin "1") (pinfunction "1_1") (pintype "passive"))
      (node (ref "R13") (pin "2") (pinfunction "2_2") (pintype "passive"))
      (node (ref "R15") (pin "1") (pinfunction "1_1") (pintype "passive"))
      (node (ref "R17") (pin "1") (pinfunction "1_1") (pintype "passive"))
    )
    (net (code "25") (name "Net-(C44-Pad1)") (class "Default")
      (node (ref "C44") (pin "1") (pinfunction "1_1") (pintype "passive"))
      (node (ref "R14") (pin "2") (pinfunction "2_2") (pintype "passive"))
      (node (ref "R24") (pin "1") (pinfunction "1_1") (pintype "passive"))
      (node (ref "R25") (pin "2") (pinfunction "2_2") (pintype "passive"))
      (node (ref "R28") (pin "2") (pinfunction "2_2") (pintype "passive"))
    )
    (net (code "26") (name "Net-(C45-Pad1)") (class "Default")
      (node (ref "C45") (pin "1") (pinfunction "1_1") (pintype "passive"))
      (node (ref "R15") (pin "2") (pinfunction "2_2") (pintype "passive"))
      (node (ref "R26") (pin "1") (pinfunction "1_1") (pintype "passive"))
      (node (ref "R27") (pin "2") (pinfunction "2_2") (pintype "passive"))
      (node (ref "R29") (pin "1") (pinfunction "1_1") (pintype "passive"))
    )
    (net (code "27") (name "Net-(D1-A)") (class "Default")
      (node (ref "D1") (pin "1") (pinfunction "A_1") (pintype "passive"))
      (node (ref "Q5") (pin "3") (pinfunction "B_3") (pintype "passive"))
      (node (ref "R18") (pin "1") (pinfunction "1_1") (pintype "passive"))
    )
    (net (code "28") (name "Net-(D1-K)") (class "Default")
      (node (ref "D1") (pin "2") (pinfunction "K_2") (pintype "passive"))
      (node (ref "D2") (pin "1") (pinfunction "A_1") (pintype "passive"))
      (node (ref "IC10") (pin "1") (pinfunction "OUT_1") (pintype "output"))
    )
    (net (code "29") (name "Net-(D2-K)") (class "Default")
      (node (ref "D2") (pin "2") (pinfunction "K_2") (pintype "passive"))
      (node (ref "Q6") (pin "3") (pinfunction "B_3") (pintype "passive"))
      (node (ref "R20") (pin "2") (pinfunction "2_2") (pintype "passive"))
    )
    (net (code "30") (name "Net-(D3-A)") (class "Default")
      (node (ref "D3") (pin "1") (pinfunction "A_1") (pintype "passive"))
      (node (ref "Q7") (pin "3") (pinfunction "B_3") (pintype "passive"))
      (node (ref "R19") (pin "1") (pinfunction "1_1") (pintype "passive"))
    )
    (net (code "31") (name "Net-(D3-K)") (class "Default")
      (node (ref "D3") (pin "2") (pinfunction "K_2") (pintype "passive"))
      (node (ref "D4") (pin "1") (pinfunction "A_1") (pintype "passive"))
      (node (ref "IC10") (pin "7") (pinfunction "OUT_7") (pintype "output"))
    )
    (net (code "32") (name "Net-(D4-K)") (class "Default")
      (node (ref "D4") (pin "2") (pinfunction "K_2") (pintype "passive"))
      (node (ref "Q8") (pin "3") (pinfunction "B_3") (pintype "passive"))
      (node (ref "R21") (pin "2") (pinfunction "2_2") (pintype "passive"))
    )
    (net (code "33") (name "Net-(IC1-IN)") (class "Default")
      (node (ref "C1") (pin "1") (pinfunction "1_1") (pintype "passive"))
      (node (ref "IC1") (pin "1") (pinfunction "IN_1") (pintype "power_in"))
      (node (ref "R1") (pin "2") (pinfunction "2_2") (pintype "passive"))
    )
    (net (code "34") (name "Net-(IC1-OUT)") (class "Default")
      (node (ref "C2") (pin "1") (pinfunction "1_1") (pintype "passive"))
      (node (ref "C3") (pin "1") (pinfunction "1_1") (pintype "passive"))
      (node (ref "C4") (pin "1") (pinfunction "1_1") (pintype "passive"))
      (node (ref "IC1") (pin "3") (pinfunction "OUT_3") (pintype "output"))
      (node (ref "X1") (pin "4") (pinfunction "VCC_4") (pintype "power_in"))
      (node (ref "X2") (pin "4") (pinfunction "VCC_4") (pintype "power_in"))
    )
    (net (code "35") (name "Net-(IC6-DVDD)") (class "Default")
      (node (ref "C19") (pin "1") (pinfunction "1_1") (pintype "passive"))
      (node (ref "IC6") (pin "1") (pinfunction "DVDD_1") (pintype "power_in"))
    )
    (net (code "36") (name "Net-(IC9A-+IN)") (class "Default")
      (node (ref "C37") (pin "1") (pinfunction "1_1") (pintype "passive"))
      (node (ref "IC9") (pin "3") (pinfunction "+IN_3") (pintype "input"))
      (node (ref "R5") (pin "2") (pinfunction "2_2") (pintype "passive"))
      (node (ref "R9") (pin "2") (pinfunction "2_2") (pintype "passive"))
    )
    (net (code "37") (name "Net-(IC9A--IN)") (class "Default")
      (node (ref "C36") (pin "2") (pinfunction "2_2") (pintype "passive"))
      (node (ref "IC9") (pin "2") (pinfunction "-IN_2") (pintype "input"))
      (node (ref "R4") (pin "2") (pinfunction "2_2") (pintype "passive"))
      (node (ref "R8") (pin "1") (pinfunction "1_1") (pintype "passive"))
    )
    (net (code "38") (name "Net-(IC9A-OUT)") (class "Default")
      (node (ref "C36") (pin "1") (pinfunction "1_1") (pintype "passive"))
      (node (ref "IC9") (pin "1") (pinfunction "OUT_1") (pintype "output"))
      (node (ref "R12") (pin "1") (pinfunction "1_1") (pintype "passive"))
      (node (ref "R8") (pin "2") (pinfunction "2_2") (pintype "passive"))
    )
    (net (code "39") (name "Net-(IC9B-+IN)") (class "Default")
      (node (ref "C39") (pin "1") (pinfunction "1_1") (pintype "passive"))
      (node (ref "IC9") (pin "5") (pinfunction "+IN_5") (pintype "input"))
      (node (ref "R11") (pin "2") (pinfunction "2_2") (pintype "passive"))
      (node (ref "R7") (pin "2") (pinfunction "2_2") (pintype "passive"))
    )
    (net (code "40") (name "Net-(IC9B--IN)") (class "Default")
      (node (ref "C38") (pin "2") (pinfunction "2_2") (pintype "passive"))
      (node (ref "IC9") (pin "6") (pinfunction "-IN_6") (pintype "input"))
      (node (ref "R10") (pin "1") (pinfunction "1_1") (pintype "passive"))
      (node (ref "R6") (pin "2") (pinfunction "2_2") (pintype "passive"))
    )
    (net (code "41") (name "Net-(IC9B-OUT)") (class "Default")
      (node (ref "C38") (pin "1") (pinfunction "1_1") (pintype "passive"))
      (node (ref "IC9") (pin "7") (pinfunction "OUT_7") (pintype "output"))
      (node (ref "R10") (pin "2") (pinfunction "2_2") (pintype "passive"))
      (node (ref "R13") (pin "1") (pinfunction "1_1") (pintype "passive"))
    )
    (net (code "42") (name "Net-(IC10A--IN)") (class "Default")
      (node (ref "C44") (pin "2") (pinfunction "2_2") (pintype "passive"))
      (node (ref "IC10") (pin "2") (pinfunction "-IN_2") (pintype "input"))
      (node (ref "R16") (pin "2") (pinfunction "2_2") (pintype "passive"))
    )
    (net (code "43") (name "Net-(IC10B--IN)") (class "Default")
      (node (ref "C45") (pin "2") (pinfunction "2_2") (pintype "passive"))
      (node (ref "IC10") (pin "6") (pinfunction "-IN_6") (pintype "input"))
      (node (ref "R17") (pin "2") (pinfunction "2_2") (pintype "passive"))
    )
    (net (code "44") (name "Net-(IC13-OUT)") (class "Default")
      (node (ref "C53") (pin "1") (pinfunction "1_1") (pintype "passive"))
      (node (ref "D5") (pin "K") (pinfunction "K_K") (pintype "bidirectional"))
      (node (ref "IC13") (pin "1") (pinfunction "OUT_1") (pintype "output"))
      (node (ref "SW1") (pin "6") (pinfunction "L2_6") (pintype "passive"))
    )
    (net (code "45") (name "Net-(JP2-Pad1)") (class "Default")
      (node (ref "JP2") (pin "1") (pinfunction "1_1") (pintype "passive"))
      (node (ref "R32") (pin "1") (pinfunction "1_1") (pintype "passive"))
    )
    (net (code "46") (name "Net-(JP2-Pad4)") (class "Default")
      (node (ref "JP2") (pin "4") (pinfunction "4_4") (pintype "passive"))
      (node (ref "R33") (pin "1") (pinfunction "1_1") (pintype "passive"))
    )
    (net (code "47") (name "Net-(Q5-E)") (class "Default")
      (node (ref "Q5") (pin "1") (pinfunction "E_1") (pintype "passive"))
      (node (ref "R24") (pin "2") (pinfunction "2_2") (pintype "passive"))
    )
    (net (code "48") (name "Net-(Q6-E)") (class "Default")
      (node (ref "Q6") (pin "1") (pinfunction "E_1") (pintype "passive"))
      (node (ref "R25") (pin "1") (pinfunction "1_1") (pintype "passive"))
    )
    (net (code "49") (name "Net-(Q7-E)") (class "Default")
      (node (ref "Q7") (pin "1") (pinfunction "E_1") (pintype "passive"))
      (node (ref "R26") (pin "2") (pinfunction "2_2") (pintype "passive"))
    )
    (net (code "50") (name "Net-(Q8-E)") (class "Default")
      (node (ref "Q8") (pin "1") (pinfunction "E_1") (pintype "passive"))
      (node (ref "R27") (pin "1") (pinfunction "1_1") (pintype "passive"))
    )
    (net (code "51") (name "Net-(Q9-B)") (class "Default")
      (node (ref "Q9") (pin "1") (pinfunction "B_1") (pintype "passive"))
      (node (ref "R30") (pin "2") (pinfunction "2_2") (pintype "passive"))
      (node (ref "R31") (pin "1") (pinfunction "1_1") (pintype "passive"))
    )
    (net (code "52") (name "Net-(Q9-C)") (class "Default")
      (node (ref "D5") (pin "A") (pinfunction "A_A") (pintype "bidirectional"))
      (node (ref "Q9") (pin "3") (pinfunction "C_3") (pintype "passive"))
      (node (ref "SW1") (pin "1") (pinfunction "L1_1") (pintype "passive"))
    )
    (net (code "53") (name "Net-(SW1-A1)") (class "Default")
      (node (ref "R29") (pin "2") (pinfunction "2_2") (pintype "passive"))
      (node (ref "SW1") (pin "3") (pinfunction "A1_3") (pintype "passive"))
    )
    (net (code "54") (name "Net-(SW1-A2)") (class "Default")
      (node (ref "R28") (pin "1") (pinfunction "1_1") (pintype "passive"))
      (node (ref "SW1") (pin "4") (pinfunction "A2_4") (pintype "passive"))
    )
    (net (code "55") (name "Net-(SW1-COM1)") (class "Default")
      (node (ref "JP4") (pin "4") (pinfunction "4_4") (pintype "passive"))
      (node (ref "SW1") (pin "2") (pinfunction "COM1_2") (pintype "passive"))
    )
    (net (code "56") (name "Net-(SW1-COM2)") (class "Default")
      (node (ref "JP4") (pin "1") (pinfunction "1_1") (pintype "passive"))
      (node (ref "SW1") (pin "5") (pinfunction "COM2_5") (pintype "passive"))
    )
    (net (code "57") (name "Net-(X1-OUT)") (class "Default")
      (node (ref "R2") (pin "1") (pinfunction "1_1") (pintype "passive"))
      (node (ref "X1") (pin "3") (pinfunction "OUT_3") (pintype "output"))
    )
    (net (code "58") (name "Net-(X2-OUT)") (class "Default")
      (node (ref "R3") (pin "1") (pinfunction "1_1") (pintype "passive"))
      (node (ref "X2") (pin "3") (pinfunction "OUT_3") (pintype "output"))
    )
    (net (code "59") (name "OPA_+") (class "Default")
      (node (ref "C30") (pin "1") (pinfunction "1_1") (pintype "passive"))
      (node (ref "C32") (pin "+") (pinfunction "1_+") (pintype "passive"))
      (node (ref "C34") (pin "1") (pinfunction "1_1") (pintype "passive"))
      (node (ref "C40") (pin "1") (pinfunction "1_1") (pintype "passive"))
      (node (ref "IC10") (pin "8") (pinfunction "V+_8") (pintype "power_in"))
      (node (ref "IC7") (pin "3") (pinfunction "OUT_3") (pintype "output"))
      (node (ref "IC9") (pin "8") (pinfunction "V+_8") (pintype "power_in"))
      (node (ref "TP4") (pin "1") (pinfunction "1_1") (pintype "passive"))
    )
    (net (code "60") (name "OPA_-") (class "Default")
      (node (ref "C31") (pin "2") (pinfunction "2_2") (pintype "passive"))
      (node (ref "C33") (pin "-") (pinfunction "2_-") (pintype "passive"))
      (node (ref "C35") (pin "2") (pinfunction "2_2") (pintype "passive"))
      (node (ref "C41") (pin "2") (pinfunction "2_2") (pintype "passive"))
      (node (ref "IC10") (pin "4") (pinfunction "V-_4") (pintype "power_in"))
      (node (ref "IC8") (pin "3") (pinfunction "OUT_3") (pintype "output"))
      (node (ref "IC9") (pin "4") (pinfunction "V-_4") (pintype "power_in"))
      (node (ref "TP3") (pin "1") (pinfunction "1_1") (pintype "passive"))
    )
    (net (code "61") (name "OUT_EN") (class "Default")
      (node (ref "JP1") (pin "13") (pinfunction "13_13") (pintype "passive"))
      (node (ref "R31") (pin "2") (pinfunction "2_2") (pintype "passive"))
    )
    (net (code "62") (name "SCK") (class "Default")
      (node (ref "IC6") (pin "3") (pinfunction "BCK_3") (pintype "input"))
      (node (ref "JP1") (pin "6") (pinfunction "6_6") (pintype "passive"))
    )
    (net (code "63") (name "V+") (class "Default")
      (node (ref "C10") (pin "1") (pinfunction "1_1") (pintype "passive"))
      (node (ref "C28") (pin "1") (pinfunction "1_1") (pintype "passive"))
      (node (ref "C46") (pin "1") (pinfunction "1_1") (pintype "passive"))
      (node (ref "C52") (pin "1") (pinfunction "1_1") (pintype "passive"))
      (node (ref "C54") (pin "+") (pinfunction "1_+") (pintype "passive"))
      (node (ref "C9") (pin "+") (pinfunction "1_+") (pintype "passive"))
      (node (ref "IC11") (pin "1") (pinfunction "IN_1") (pintype "power_in"))
      (node (ref "IC13") (pin "3") (pinfunction "IN_3") (pintype "power_in"))
      (node (ref "IC5") (pin "1") (pinfunction "IN_1") (pintype "power_in"))
      (node (ref "IC7") (pin "1") (pinfunction "IN_1") (pintype "power_in"))
      (node (ref "R32") (pin "2") (pinfunction "2_2") (pintype "passive"))
    )
    (net (code "64") (name "V-") (class "Default")
      (node (ref "C29") (pin "2") (pinfunction "2_2") (pintype "passive"))
      (node (ref "C47") (pin "2") (pinfunction "2_2") (pintype "passive"))
      (node (ref "C55") (pin "-") (pinfunction "2_-") (pintype "passive"))
      (node (ref "IC12") (pin "2") (pinfunction "IN_2") (pintype "input"))
      (node (ref "IC8") (pin "2") (pinfunction "IN_2") (pintype "input"))
      (node (ref "R33") (pin "2") (pinfunction "2_2") (pintype "passive"))
    )
    (net (code "65") (name "unconnected-(IC6-DIF0{slash}DZFL-Pad10)") (class "Default")
      (node (ref "IC6") (pin "10") (pinfunction "DIF0/DZFL_10") (pintype "bidirectional"))
    )
    (net (code "66") (name "unconnected-(IC6-DIF1{slash}DZFR-Pad11)") (class "Default")
      (node (ref "IC6") (pin "11") (pinfunction "DIF1/DZFR_11") (pintype "bidirectional"))
    )
    (net (code "67") (name "unconnected-(IC6-NC1-Pad24)") (class "Default")
      (node (ref "IC6") (pin "24") (pinfunction "NC1_24") (pintype "passive"))
    )
    (net (code "68") (name "unconnected-(IC6-NC2-Pad37)") (class "Default")
      (node (ref "IC6") (pin "37") (pinfunction "NC2_37") (pintype "passive"))
    )
    (net (code "69") (name "unconnected-(IC6-NC3-Pad43)") (class "Default")
      (node (ref "IC6") (pin "43") (pinfunction "NC3_43") (pintype "passive"))
    )
  )
)
